# 02_-_MCU.net
KiCad netlist of a schematic drawn in Altium Designer
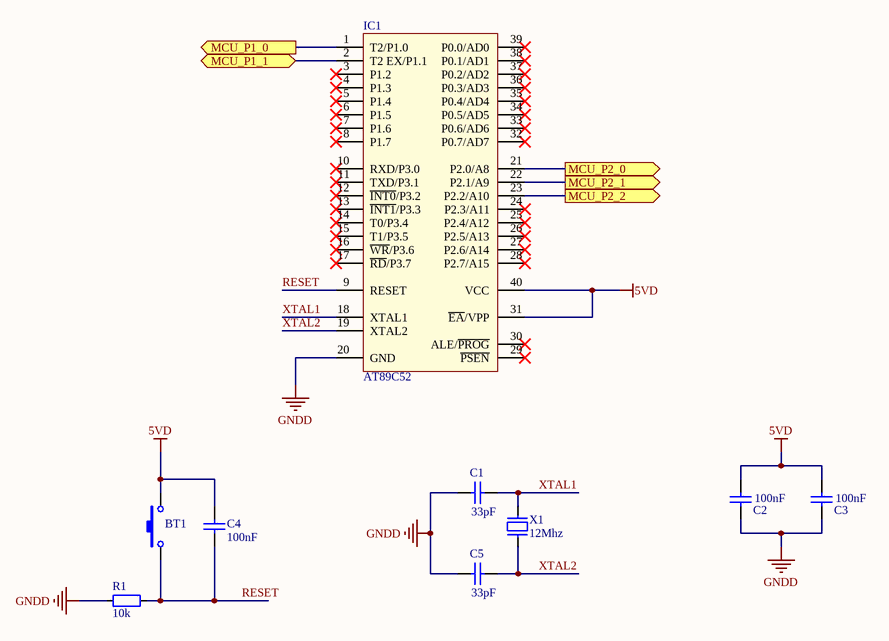
[diagram p0: [02] - MCU.SchDoc]

(export (version "E")
  (design (tool "Eeschema 10.0.6"))
  (components
    (comp (ref "BT1")
      (value "SW2")
      (footprint "SW 3x2x4")
      (description "SMD")
      (libsource (lib "THU VIEN SCH") (part "Nut Nhan 2 Chan SMD"))
    )
    (comp (ref "C1")
      (value "33pF")
      (footprint "CAP_0805")
      (description "Capacitor")
      (fields (field (name "PUBLISHER") "Altium Limited"))
      (libsource (lib "My Library") (part "CapCeramic"))
    )
    (comp (ref "C2")
      (value "100nF")
      (footprint "CAP_0805")
      (description "Capacitor")
      (fields (field (name "PUBLISHER") "Altium Limited"))
      (libsource (lib "My Library") (part "CapSMD"))
    )
    (comp (ref "C3")
      (value "100nF")
      (footprint "CAP_0805")
      (description "Capacitor")
      (fields (field (name "PUBLISHER") "Altium Limited"))
      (libsource (lib "My Library") (part "CapSMD"))
    )
    (comp (ref "C4")
      (value "100nF")
      (footprint "CAP_0805")
      (description "Capacitor")
      (fields (field (name "PUBLISHER") "Altium Limited"))
      (libsource (lib "My Library") (part "CapCeramic"))
    )
    (comp (ref "C5")
      (value "33pF")
      (footprint "CAP_0805")
      (description "Capacitor")
      (fields (field (name "PUBLISHER") "Altium Limited"))
      (libsource (lib "My Library") (part "CapCeramic"))
    )
    (comp (ref "IC1")
      (value "AT89C52")
      (footprint "DIP40/W0.6")
      (description "Atmel AT89C52, 8k Byte Flash Memory , 40 Pin")
      (libsource (lib "My Library") (part "AT89C52"))
    )
    (comp (ref "R1")
      (value "10k")
      (footprint "RES-SMD-0805")
      (description "Resistor")
      (fields
        (field (name "MANUFACTURER") "Generic Components")
        (field (name "PUBLISHER") "Altium Hobart Technology Centre")
      )
      (libsource (lib "My Library") (part "Resistor - SMD"))
    )
    (comp (ref "X1")
      (value "12Mhz")
      (footprint "XT2")
      (description "Crystal For all Crystal 2pin.")
      (libsource (lib "My Library") (part "XT2"))
    )
  )
  (nets
    (net (code "1") (name "/MCU_P1_0") (class "Default")
      (node (ref "IC1") (pin "1") (pinfunction "T2/P1.0_1") (pintype "passive"))
    )
    (net (code "2") (name "/MCU_P1_1") (class "Default")
      (node (ref "IC1") (pin "2") (pinfunction "T2_EX/P1.1_2") (pintype "passive"))
    )
    (net (code "3") (name "/MCU_P2_0") (class "Default")
      (node (ref "IC1") (pin "21") (pinfunction "P2.0/A8_21") (pintype "passive"))
    )
    (net (code "4") (name "/MCU_P2_1") (class "Default")
      (node (ref "IC1") (pin "22") (pinfunction "P2.1/A9_22") (pintype "passive"))
    )
    (net (code "5") (name "/MCU_P2_2") (class "Default")
      (node (ref "IC1") (pin "23") (pinfunction "P2.2/A10_23") (pintype "passive"))
    )
    (net (code "6") (name "/RESET") (class "Default")
      (node (ref "BT1") (pin "1") (pinfunction "1_1") (pintype "passive"))
      (node (ref "C4") (pin "1") (pinfunction "1_1") (pintype "passive"))
      (node (ref "IC1") (pin "9") (pinfunction "RESET_9") (pintype "passive"))
      (node (ref "R1") (pin "1") (pinfunction "1_1") (pintype "passive"))
    )
    (net (code "7") (name "/XTAL1") (class "Default")
      (node (ref "C1") (pin "2") (pinfunction "2_2") (pintype "passive"))
      (node (ref "IC1") (pin "18") (pinfunction "XTAL1_18") (pintype "passive"))
      (node (ref "X1") (pin "1") (pinfunction "1_1") (pintype "passive"))
    )
    (net (code "8") (name "/XTAL2") (class "Default")
      (node (ref "C5") (pin "2") (pinfunction "2_2") (pintype "passive"))
      (node (ref "IC1") (pin "19") (pinfunction "XTAL2_19") (pintype "passive"))
      (node (ref "X1") (pin "2") (pinfunction "2_2") (pintype "passive"))
    )
    (net (code "9") (name "5VD") (class "Default")
      (node (ref "BT1") (pin "2") (pinfunction "2_2") (pintype "passive"))
      (node (ref "C2") (pin "2") (pinfunction "2_2") (pintype "passive"))
      (node (ref "C3") (pin "2") (pinfunction "2_2") (pintype "passive"))
      (node (ref "C4") (pin "2") (pinfunction "2_2") (pintype "passive"))
      (node (ref "IC1") (pin "31") (pinfunction "~{EA}/VPP_31") (pintype "passive"))
      (node (ref "IC1") (pin "40") (pinfunction "VCC_40") (pintype "power_in"))
    )
    (net (code "10") (name "GNDD") (class "Default")
      (node (ref "C1") (pin "1") (pinfunction "1_1") (pintype "passive"))
      (node (ref "C2") (pin "1") (pinfunction "1_1") (pintype "passive"))
      (node (ref "C3") (pin "1") (pinfunction "1_1") (pintype "passive"))
      (node (ref "C5") (pin "1") (pinfunction "1_1") (pintype "passive"))
      (node (ref "IC1") (pin "20") (pinfunction "GND_20") (pintype "open_emitter"))
      (node (ref "R1") (pin "2") (pinfunction "2_2") (pintype "passive"))
    )
    (net (code "11") (name "unconnected-(IC1-ALE{slash}~{PROG}-Pad30)") (class "Default")
      (node (ref "IC1") (pin "30") (pinfunction "ALE/~{PROG}_30") (pintype "passive+no_connect"))
    )
    (net (code "12") (name "unconnected-(IC1-P0.0{slash}AD0-Pad39)") (class "Default")
      (node (ref "IC1") (pin "39") (pinfunction "P0.0/AD0_39") (pintype "passive+no_connect"))
    )
    (net (code "13") (name "unconnected-(IC1-P0.1{slash}AD1-Pad38)") (class "Default")
      (node (ref "IC1") (pin "38") (pinfunction "P0.1/AD1_38") (pintype "passive+no_connect"))
    )
    (net (code "14") (name "unconnected-(IC1-P0.2{slash}AD2-Pad37)") (class "Default")
      (node (ref "IC1") (pin "37") (pinfunction "P0.2/AD2_37") (pintype "passive+no_connect"))
    )
    (net (code "15") (name "unconnected-(IC1-P0.3{slash}AD3-Pad36)") (class "Default")
      (node (ref "IC1") (pin "36") (pinfunction "P0.3/AD3_36") (pintype "passive+no_connect"))
    )
    (net (code "16") (name "unconnected-(IC1-P0.4{slash}AD4-Pad35)") (class "Default")
      (node (ref "IC1") (pin "35") (pinfunction "P0.4/AD4_35") (pintype "passive+no_connect"))
    )
    (net (code "17") (name "unconnected-(IC1-P0.5{slash}AD5-Pad34)") (class "Default")
      (node (ref "IC1") (pin "34") (pinfunction "P0.5/AD5_34") (pintype "passive+no_connect"))
    )
    (net (code "18") (name "unconnected-(IC1-P0.6{slash}AD6-Pad33)") (class "Default")
      (node (ref "IC1") (pin "33") (pinfunction "P0.6/AD6_33") (pintype "passive+no_connect"))
    )
    (net (code "19") (name "unconnected-(IC1-P0.7{slash}AD7-Pad32)") (class "Default")
      (node (ref "IC1") (pin "32") (pinfunction "P0.7/AD7_32") (pintype "passive+no_connect"))
    )
    (net (code "20") (name "unconnected-(IC1-P1.2-Pad3)") (class "Default")
      (node (ref "IC1") (pin "3") (pinfunction "P1.2_3") (pintype "passive+no_connect"))
    )
    (net (code "21") (name "unconnected-(IC1-P1.3-Pad4)") (class "Default")
      (node (ref "IC1") (pin "4") (pinfunction "P1.3_4") (pintype "passive+no_connect"))
    )
    (net (code "22") (name "unconnected-(IC1-P1.4-Pad5)") (class "Default")
      (node (ref "IC1") (pin "5") (pinfunction "P1.4_5") (pintype "passive+no_connect"))
    )
    (net (code "23") (name "unconnected-(IC1-P1.5-Pad6)") (class "Default")
      (node (ref "IC1") (pin "6") (pinfunction "P1.5_6") (pintype "passive+no_connect"))
    )
    (net (code "24") (name "unconnected-(IC1-P1.6-Pad7)") (class "Default")
      (node (ref "IC1") (pin "7") (pinfunction "P1.6_7") (pintype "passive+no_connect"))
    )
    (net (code "25") (name "unconnected-(IC1-P1.7-Pad8)") (class "Default")
      (node (ref "IC1") (pin "8") (pinfunction "P1.7_8") (pintype "passive+no_connect"))
    )
    (net (code "26") (name "unconnected-(IC1-P2.3{slash}A11-Pad24)") (class "Default")
      (node (ref "IC1") (pin "24") (pinfunction "P2.3/A11_24") (pintype "passive+no_connect"))
    )
    (net (code "27") (name "unconnected-(IC1-P2.4{slash}A12-Pad25)") (class "Default")
      (node (ref "IC1") (pin "25") (pinfunction "P2.4/A12_25") (pintype "passive+no_connect"))
    )
    (net (code "28") (name "unconnected-(IC1-P2.5{slash}A13-Pad26)") (class "Default")
      (node (ref "IC1") (pin "26") (pinfunction "P2.5/A13_26") (pintype "passive+no_connect"))
    )
    (net (code "29") (name "unconnected-(IC1-P2.6{slash}A14-Pad27)") (class "Default")
      (node (ref "IC1") (pin "27") (pinfunction "P2.6/A14_27") (pintype "passive+no_connect"))
    )
    (net (code "30") (name "unconnected-(IC1-P2.7{slash}A15-Pad28)") (class "Default")
      (node (ref "IC1") (pin "28") (pinfunction "P2.7/A15_28") (pintype "passive+no_connect"))
    )
    (net (code "31") (name "unconnected-(IC1-RXD{slash}P3.0-Pad10)") (class "Default")
      (node (ref "IC1") (pin "10") (pinfunction "RXD/P3.0_10") (pintype "passive+no_connect"))
    )
    (net (code "32") (name "unconnected-(IC1-T0{slash}P3.4-Pad14)") (class "Default")
      (node (ref "IC1") (pin "14") (pinfunction "T0/P3.4_14") (pintype "passive+no_connect"))
    )
    (net (code "33") (name "unconnected-(IC1-T1{slash}P3.5-Pad15)") (class "Default")
      (node (ref "IC1") (pin "15") (pinfunction "T1/P3.5_15") (pintype "passive+no_connect"))
    )
    (net (code "34") (name "unconnected-(IC1-TXD{slash}P3.1-Pad11)") (class "Default")
      (node (ref "IC1") (pin "11") (pinfunction "TXD/P3.1_11") (pintype "passive+no_connect"))
    )
    (net (code "35") (name "unconnected-(IC1-~{INT0}{slash}P3.2-Pad12)") (class "Default")
      (node (ref "IC1") (pin "12") (pinfunction "~{INT0}/P3.2_12") (pintype "passive+no_connect"))
    )
    (net (code "36") (name "unconnected-(IC1-~{INT1}{slash}P3.3-Pad13)") (class "Default")
      (node (ref "IC1") (pin "13") (pinfunction "~{INT1}/P3.3_13") (pintype "passive+no_connect"))
    )
    (net (code "37") (name "unconnected-(IC1-~{PSEN}-Pad29)") (class "Default")
      (node (ref "IC1") (pin "29") (pinfunction "~{PSEN}_29") (pintype "passive+no_connect"))
    )
    (net (code "38") (name "unconnected-(IC1-~{RD}{slash}P3.7-Pad17)") (class "Default")
      (node (ref "IC1") (pin "17") (pinfunction "~{RD}/P3.7_17") (pintype "passive+no_connect"))
    )
    (net (code "39") (name "unconnected-(IC1-~{WR}{slash}P3.6-Pad16)") (class "Default")
      (node (ref "IC1") (pin "16") (pinfunction "~{WR}/P3.6_16") (pintype "passive+no_connect"))
    )
  )
)
